# FUSE.net
KiCad netlist of a schematic drawn in EAGLE
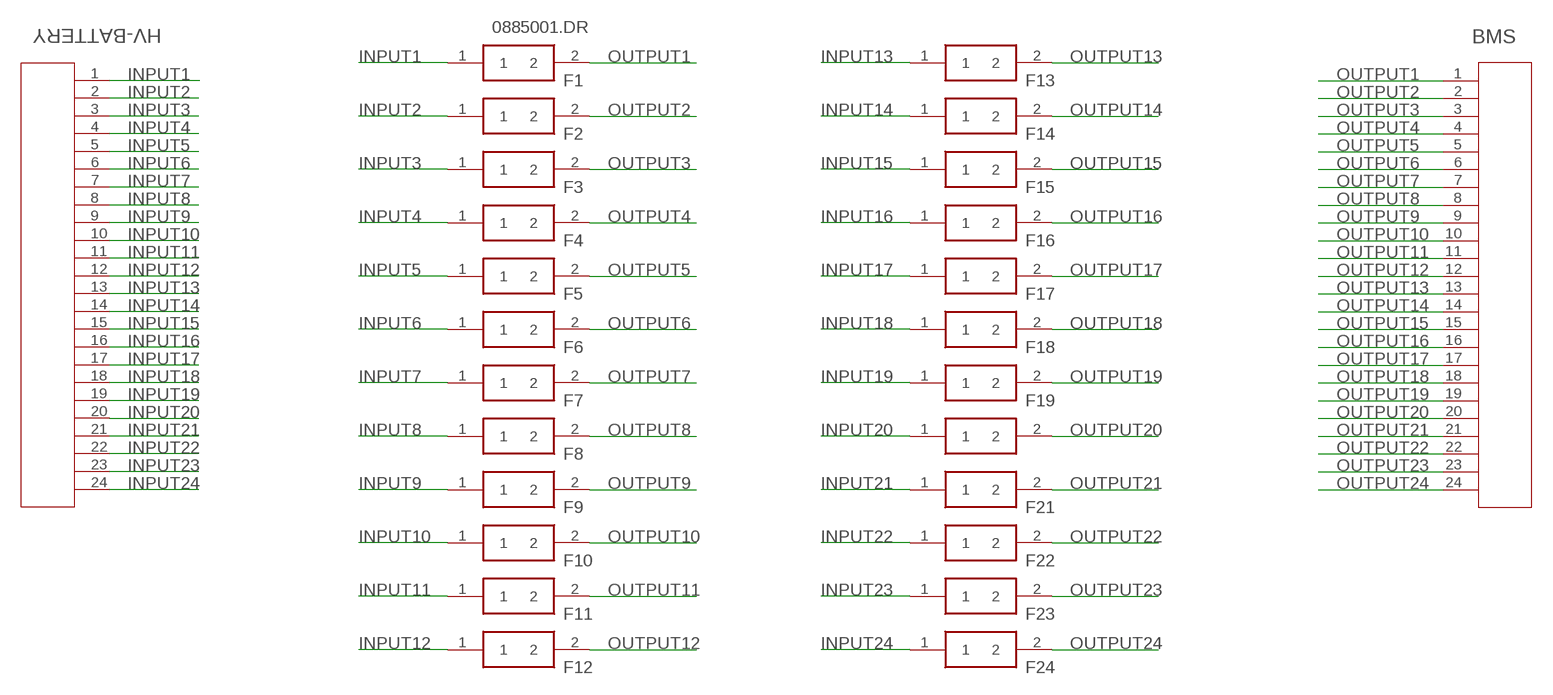
[diagram p0: schematic, sheet 1]

(export (version "E")
  (design (tool "Eeschema 10.0.6"))
  (components
    (comp (ref "BMS")
      (value "24P(90DEG)_1-794108-0")
      (footprint "eagle-import:CON24_2X12_P4_14MM_RAMNL")
      (fields (field (name "MANUFACTURER_PART_NUMBER") "17941080"))
      (libsource (lib "eagle-import") (part "24P(90DEG)_1-794108-0"))
    )
    (comp (ref "F1")
      (value "0885001.DR")
      (footprint "eagle-import:FUSC10948X488N")
      (fields (field (name "MOUSER_PART_NUMBER") "576-0885001.DR"))
      (libsource (lib "eagle-import") (part "0885001.DR"))
    )
    (comp (ref "F2")
      (value "0885001.DR")
      (footprint "eagle-import:FUSC10948X488N")
      (fields (field (name "MOUSER_PART_NUMBER") "576-0885001.DR"))
      (libsource (lib "eagle-import") (part "0885001.DR"))
    )
    (comp (ref "F3")
      (value "0885001.DR")
      (footprint "eagle-import:FUSC10948X488N")
      (fields (field (name "MOUSER_PART_NUMBER") "576-0885001.DR"))
      (libsource (lib "eagle-import") (part "0885001.DR"))
    )
    (comp (ref "F4")
      (value "0885001.DR")
      (footprint "eagle-import:FUSC10948X488N")
      (fields (field (name "MOUSER_PART_NUMBER") "576-0885001.DR"))
      (libsource (lib "eagle-import") (part "0885001.DR"))
    )
    (comp (ref "F5")
      (value "0885001.DR")
      (footprint "eagle-import:FUSC10948X488N")
      (fields (field (name "MOUSER_PART_NUMBER") "576-0885001.DR"))
      (libsource (lib "eagle-import") (part "0885001.DR"))
    )
    (comp (ref "F6")
      (value "0885001.DR")
      (footprint "eagle-import:FUSC10948X488N")
      (fields (field (name "MOUSER_PART_NUMBER") "576-0885001.DR"))
      (libsource (lib "eagle-import") (part "0885001.DR"))
    )
    (comp (ref "F7")
      (value "0885001.DR")
      (footprint "eagle-import:FUSC10948X488N")
      (fields (field (name "MOUSER_PART_NUMBER") "576-0885001.DR"))
      (libsource (lib "eagle-import") (part "0885001.DR"))
    )
    (comp (ref "F8")
      (value "0885001.DR")
      (footprint "eagle-import:FUSC10948X488N")
      (fields (field (name "MOUSER_PART_NUMBER") "576-0885001.DR"))
      (libsource (lib "eagle-import") (part "0885001.DR"))
    )
    (comp (ref "F9")
      (value "0885001.DR")
      (footprint "eagle-import:FUSC10948X488N")
      (fields (field (name "MOUSER_PART_NUMBER") "576-0885001.DR"))
      (libsource (lib "eagle-import") (part "0885001.DR"))
    )
    (comp (ref "F10")
      (value "0885001.DR")
      (footprint "eagle-import:FUSC10948X488N")
      (fields (field (name "MOUSER_PART_NUMBER") "576-0885001.DR"))
      (libsource (lib "eagle-import") (part "0885001.DR"))
    )
    (comp (ref "F11")
      (value "0885001.DR")
      (footprint "eagle-import:FUSC10948X488N")
      (fields (field (name "MOUSER_PART_NUMBER") "576-0885001.DR"))
      (libsource (lib "eagle-import") (part "0885001.DR"))
    )
    (comp (ref "F12")
      (value "0885001.DR")
      (footprint "eagle-import:FUSC10948X488N")
      (fields (field (name "MOUSER_PART_NUMBER") "576-0885001.DR"))
      (libsource (lib "eagle-import") (part "0885001.DR"))
    )
    (comp (ref "F13")
      (value "0885001.DR")
      (footprint "eagle-import:FUSC10948X488N")
      (fields (field (name "MOUSER_PART_NUMBER") "576-0885001.DR"))
      (libsource (lib "eagle-import") (part "0885001.DR"))
    )
    (comp (ref "F14")
      (value "0885001.DR")
      (footprint "eagle-import:FUSC10948X488N")
      (fields (field (name "MOUSER_PART_NUMBER") "576-0885001.DR"))
      (libsource (lib "eagle-import") (part "0885001.DR"))
    )
    (comp (ref "F15")
      (value "0885001.DR")
      (footprint "eagle-import:FUSC10948X488N")
      (fields (field (name "MOUSER_PART_NUMBER") "576-0885001.DR"))
      (libsource (lib "eagle-import") (part "0885001.DR"))
    )
    (comp (ref "F16")
      (value "0885001.DR")
      (footprint "eagle-import:FUSC10948X488N")
      (fields (field (name "MOUSER_PART_NUMBER") "576-0885001.DR"))
      (libsource (lib "eagle-import") (part "0885001.DR"))
    )
    (comp (ref "F17")
      (value "0885001.DR")
      (footprint "eagle-import:FUSC10948X488N")
      (fields (field (name "MOUSER_PART_NUMBER") "576-0885001.DR"))
      (libsource (lib "eagle-import") (part "0885001.DR"))
    )
    (comp (ref "F18")
      (value "0885001.DR")
      (footprint "eagle-import:FUSC10948X488N")
      (fields (field (name "MOUSER_PART_NUMBER") "576-0885001.DR"))
      (libsource (lib "eagle-import") (part "0885001.DR"))
    )
    (comp (ref "F19")
      (value "0885001.DR")
      (footprint "eagle-import:FUSC10948X488N")
      (fields (field (name "MOUSER_PART_NUMBER") "576-0885001.DR"))
      (libsource (lib "eagle-import") (part "0885001.DR"))
    )
    (comp (ref "F20")
      (value "0885001.DR")
      (footprint "eagle-import:FUSC10948X488N")
      (fields (field (name "MOUSER_PART_NUMBER") "576-0885001.DR"))
      (libsource (lib "eagle-import") (part "0885001.DR"))
    )
    (comp (ref "F21")
      (value "0885001.DR")
      (footprint "eagle-import:FUSC10948X488N")
      (fields (field (name "MOUSER_PART_NUMBER") "576-0885001.DR"))
      (libsource (lib "eagle-import") (part "0885001.DR"))
    )
    (comp (ref "F22")
      (value "0885001.DR")
      (footprint "eagle-import:FUSC10948X488N")
      (fields (field (name "MOUSER_PART_NUMBER") "576-0885001.DR"))
      (libsource (lib "eagle-import") (part "0885001.DR"))
    )
    (comp (ref "F23")
      (value "0885001.DR")
      (footprint "eagle-import:FUSC10948X488N")
      (fields (field (name "MOUSER_PART_NUMBER") "576-0885001.DR"))
      (libsource (lib "eagle-import") (part "0885001.DR"))
    )
    (comp (ref "F24")
      (value "0885001.DR")
      (footprint "eagle-import:FUSC10948X488N")
      (fields (field (name "MOUSER_PART_NUMBER") "576-0885001.DR"))
      (libsource (lib "eagle-import") (part "0885001.DR"))
    )
    (comp (ref "HV-BATTERY")
      (value "24P(90DEG)_1-794108-0")
      (footprint "eagle-import:CON24_2X12_P4_14MM_RAMNL")
      (fields (field (name "MANUFACTURER_PART_NUMBER") "17941080"))
      (libsource (lib "eagle-import") (part "24P(90DEG)_1-794108-0"))
    )
  )
  (nets
    (net (code "1") (name "/INPUT1") (class "Default")
      (node (ref "F1") (pin "1") (pinfunction "1_1") (pintype "bidirectional"))
      (node (ref "HV-BATTERY") (pin "1") (pinfunction "1_1") (pintype "passive"))
    )
    (net (code "2") (name "/INPUT2") (class "Default")
      (node (ref "F2") (pin "1") (pinfunction "1_1") (pintype "bidirectional"))
      (node (ref "HV-BATTERY") (pin "2") (pinfunction "2_2") (pintype "passive"))
    )
    (net (code "3") (name "/INPUT3") (class "Default")
      (node (ref "F3") (pin "1") (pinfunction "1_1") (pintype "bidirectional"))
      (node (ref "HV-BATTERY") (pin "3") (pinfunction "3_3") (pintype "passive"))
    )
    (net (code "4") (name "/INPUT4") (class "Default")
      (node (ref "F4") (pin "1") (pinfunction "1_1") (pintype "bidirectional"))
      (node (ref "HV-BATTERY") (pin "4") (pinfunction "4_4") (pintype "passive"))
    )
    (net (code "5") (name "/INPUT5") (class "Default")
      (node (ref "F5") (pin "1") (pinfunction "1_1") (pintype "bidirectional"))
      (node (ref "HV-BATTERY") (pin "5") (pinfunction "5_5") (pintype "passive"))
    )
    (net (code "6") (name "/INPUT6") (class "Default")
      (node (ref "F6") (pin "1") (pinfunction "1_1") (pintype "bidirectional"))
      (node (ref "HV-BATTERY") (pin "6") (pinfunction "6_6") (pintype "passive"))
    )
    (net (code "7") (name "/INPUT7") (class "Default")
      (node (ref "F7") (pin "1") (pinfunction "1_1") (pintype "bidirectional"))
      (node (ref "HV-BATTERY") (pin "7") (pinfunction "7_7") (pintype "passive"))
    )
    (net (code "8") (name "/INPUT8") (class "Default")
      (node (ref "F8") (pin "1") (pinfunction "1_1") (pintype "bidirectional"))
      (node (ref "HV-BATTERY") (pin "8") (pinfunction "8_8") (pintype "passive"))
    )
    (net (code "9") (name "/INPUT9") (class "Default")
      (node (ref "F9") (pin "1") (pinfunction "1_1") (pintype "bidirectional"))
      (node (ref "HV-BATTERY") (pin "9") (pinfunction "9_9") (pintype "passive"))
    )
    (net (code "10") (name "/INPUT10") (class "Default")
      (node (ref "F10") (pin "1") (pinfunction "1_1") (pintype "bidirectional"))
      (node (ref "HV-BATTERY") (pin "10") (pinfunction "10_10") (pintype "passive"))
    )
    (net (code "11") (name "/INPUT11") (class "Default")
      (node (ref "F11") (pin "1") (pinfunction "1_1") (pintype "bidirectional"))
      (node (ref "HV-BATTERY") (pin "11") (pinfunction "11_11") (pintype "passive"))
    )
    (net (code "12") (name "/INPUT12") (class "Default")
      (node (ref "F12") (pin "1") (pinfunction "1_1") (pintype "bidirectional"))
      (node (ref "HV-BATTERY") (pin "12") (pinfunction "12_12") (pintype "passive"))
    )
    (net (code "13") (name "/INPUT13") (class "Default")
      (node (ref "F13") (pin "1") (pinfunction "1_1") (pintype "bidirectional"))
      (node (ref "HV-BATTERY") (pin "13") (pinfunction "13_13") (pintype "passive"))
    )
    (net (code "14") (name "/INPUT14") (class "Default")
      (node (ref "F14") (pin "1") (pinfunction "1_1") (pintype "bidirectional"))
      (node (ref "HV-BATTERY") (pin "14") (pinfunction "14_14") (pintype "passive"))
    )
    (net (code "15") (name "/INPUT15") (class "Default")
      (node (ref "F15") (pin "1") (pinfunction "1_1") (pintype "bidirectional"))
      (node (ref "HV-BATTERY") (pin "15") (pinfunction "15_15") (pintype "passive"))
    )
    (net (code "16") (name "/INPUT16") (class "Default")
      (node (ref "F16") (pin "1") (pinfunction "1_1") (pintype "bidirectional"))
      (node (ref "HV-BATTERY") (pin "16") (pinfunction "16_16") (pintype "passive"))
    )
    (net (code "17") (name "/INPUT17") (class "Default")
      (node (ref "F17") (pin "1") (pinfunction "1_1") (pintype "bidirectional"))
      (node (ref "HV-BATTERY") (pin "17") (pinfunction "17_17") (pintype "passive"))
    )
    (net (code "18") (name "/INPUT18") (class "Default")
      (node (ref "F18") (pin "1") (pinfunction "1_1") (pintype "bidirectional"))
      (node (ref "HV-BATTERY") (pin "18") (pinfunction "18_18") (pintype "passive"))
    )
    (net (code "19") (name "/INPUT19") (class "Default")
      (node (ref "F19") (pin "1") (pinfunction "1_1") (pintype "bidirectional"))
      (node (ref "HV-BATTERY") (pin "19") (pinfunction "19_19") (pintype "passive"))
    )
    (net (code "20") (name "/INPUT20") (class "Default")
      (node (ref "F20") (pin "1") (pinfunction "1_1") (pintype "bidirectional"))
      (node (ref "HV-BATTERY") (pin "20") (pinfunction "20_20") (pintype "passive"))
    )
    (net (code "21") (name "/INPUT21") (class "Default")
      (node (ref "F21") (pin "1") (pinfunction "1_1") (pintype "bidirectional"))
      (node (ref "HV-BATTERY") (pin "21") (pinfunction "21_21") (pintype "passive"))
    )
    (net (code "22") (name "/INPUT22") (class "Default")
      (node (ref "F22") (pin "1") (pinfunction "1_1") (pintype "bidirectional"))
      (node (ref "HV-BATTERY") (pin "22") (pinfunction "22_22") (pintype "passive"))
    )
    (net (code "23") (name "/INPUT23") (class "Default")
      (node (ref "F23") (pin "1") (pinfunction "1_1") (pintype "bidirectional"))
      (node (ref "HV-BATTERY") (pin "23") (pinfunction "23_23") (pintype "passive"))
    )
    (net (code "24") (name "/INPUT24") (class "Default")
      (node (ref "F24") (pin "1") (pinfunction "1_1") (pintype "bidirectional"))
      (node (ref "HV-BATTERY") (pin "24") (pinfunction "24_24") (pintype "passive"))
    )
    (net (code "25") (name "/OUTPUT1") (class "Default")
      (node (ref "BMS") (pin "1") (pinfunction "1_1") (pintype "passive"))
      (node (ref "F1") (pin "2") (pinfunction "2_2") (pintype "bidirectional"))
    )
    (net (code "26") (name "/OUTPUT2") (class "Default")
      (node (ref "BMS") (pin "2") (pinfunction "2_2") (pintype "passive"))
      (node (ref "F2") (pin "2") (pinfunction "2_2") (pintype "bidirectional"))
    )
    (net (code "27") (name "/OUTPUT3") (class "Default")
      (node (ref "BMS") (pin "3") (pinfunction "3_3") (pintype "passive"))
      (node (ref "F3") (pin "2") (pinfunction "2_2") (pintype "bidirectional"))
    )
    (net (code "28") (name "/OUTPUT4") (class "Default")
      (node (ref "BMS") (pin "4") (pinfunction "4_4") (pintype "passive"))
      (node (ref "F4") (pin "2") (pinfunction "2_2") (pintype "bidirectional"))
    )
    (net (code "29") (name "/OUTPUT5") (class "Default")
      (node (ref "BMS") (pin "5") (pinfunction "5_5") (pintype "passive"))
      (node (ref "F5") (pin "2") (pinfunction "2_2") (pintype "bidirectional"))
    )
    (net (code "30") (name "/OUTPUT6") (class "Default")
      (node (ref "BMS") (pin "6") (pinfunction "6_6") (pintype "passive"))
      (node (ref "F6") (pin "2") (pinfunction "2_2") (pintype "bidirectional"))
    )
    (net (code "31") (name "/OUTPUT7") (class "Default")
      (node (ref "BMS") (pin "7") (pinfunction "7_7") (pintype "passive"))
      (node (ref "F7") (pin "2") (pinfunction "2_2") (pintype "bidirectional"))
    )
    (net (code "32") (name "/OUTPUT8") (class "Default")
      (node (ref "BMS") (pin "8") (pinfunction "8_8") (pintype "passive"))
      (node (ref "F8") (pin "2") (pinfunction "2_2") (pintype "bidirectional"))
    )
    (net (code "33") (name "/OUTPUT9") (class "Default")
      (node (ref "BMS") (pin "9") (pinfunction "9_9") (pintype "passive"))
      (node (ref "F9") (pin "2") (pinfunction "2_2") (pintype "bidirectional"))
    )
    (net (code "34") (name "/OUTPUT10") (class "Default")
      (node (ref "BMS") (pin "10") (pinfunction "10_10") (pintype "passive"))
      (node (ref "F10") (pin "2") (pinfunction "2_2") (pintype "bidirectional"))
    )
    (net (code "35") (name "/OUTPUT11") (class "Default")
      (node (ref "BMS") (pin "11") (pinfunction "11_11") (pintype "passive"))
      (node (ref "F11") (pin "2") (pinfunction "2_2") (pintype "bidirectional"))
    )
    (net (code "36") (name "/OUTPUT12") (class "Default")
      (node (ref "BMS") (pin "12") (pinfunction "12_12") (pintype "passive"))
      (node (ref "F12") (pin "2") (pinfunction "2_2") (pintype "bidirectional"))
    )
    (net (code "37") (name "/OUTPUT13") (class "Default")
      (node (ref "BMS") (pin "13") (pinfunction "13_13") (pintype "passive"))
      (node (ref "F13") (pin "2") (pinfunction "2_2") (pintype "bidirectional"))
    )
    (net (code "38") (name "/OUTPUT14") (class "Default")
      (node (ref "BMS") (pin "14") (pinfunction "14_14") (pintype "passive"))
      (node (ref "F14") (pin "2") (pinfunction "2_2") (pintype "bidirectional"))
    )
    (net (code "39") (name "/OUTPUT15") (class "Default")
      (node (ref "BMS") (pin "15") (pinfunction "15_15") (pintype "passive"))
      (node (ref "F15") (pin "2") (pinfunction "2_2") (pintype "bidirectional"))
    )
    (net (code "40") (name "/OUTPUT16") (class "Default")
      (node (ref "BMS") (pin "16") (pinfunction "16_16") (pintype "passive"))
      (node (ref "F16") (pin "2") (pinfunction "2_2") (pintype "bidirectional"))
    )
    (net (code "41") (name "/OUTPUT17") (class "Default")
      (node (ref "BMS") (pin "17") (pinfunction "17_17") (pintype "passive"))
      (node (ref "F17") (pin "2") (pinfunction "2_2") (pintype "bidirectional"))
    )
    (net (code "42") (name "/OUTPUT18") (class "Default")
      (node (ref "BMS") (pin "18") (pinfunction "18_18") (pintype "passive"))
      (node (ref "F18") (pin "2") (pinfunction "2_2") (pintype "bidirectional"))
    )
    (net (code "43") (name "/OUTPUT19") (class "Default")
      (node (ref "BMS") (pin "19") (pinfunction "19_19") (pintype "passive"))
      (node (ref "F19") (pin "2") (pinfunction "2_2") (pintype "bidirectional"))
    )
    (net (code "44") (name "/OUTPUT20") (class "Default")
      (node (ref "BMS") (pin "20") (pinfunction "20_20") (pintype "passive"))
      (node (ref "F20") (pin "2") (pinfunction "2_2") (pintype "bidirectional"))
    )
    (net (code "45") (name "/OUTPUT21") (class "Default")
      (node (ref "BMS") (pin "21") (pinfunction "21_21") (pintype "passive"))
      (node (ref "F21") (pin "2") (pinfunction "2_2") (pintype "bidirectional"))
    )
    (net (code "46") (name "/OUTPUT22") (class "Default")
      (node (ref "BMS") (pin "22") (pinfunction "22_22") (pintype "passive"))
      (node (ref "F22") (pin "2") (pinfunction "2_2") (pintype "bidirectional"))
    )
    (net (code "47") (name "/OUTPUT23") (class "Default")
      (node (ref "BMS") (pin "23") (pinfunction "23_23") (pintype "passive"))
      (node (ref "F23") (pin "2") (pinfunction "2_2") (pintype "bidirectional"))
    )
    (net (code "48") (name "/OUTPUT24") (class "Default")
      (node (ref "BMS") (pin "24") (pinfunction "24_24") (pintype "passive"))
      (node (ref "F24") (pin "2") (pinfunction "2_2") (pintype "bidirectional"))
    )
  )
)
